# thesis.net
KiCad netlist of a schematic drawn in Altium Designer
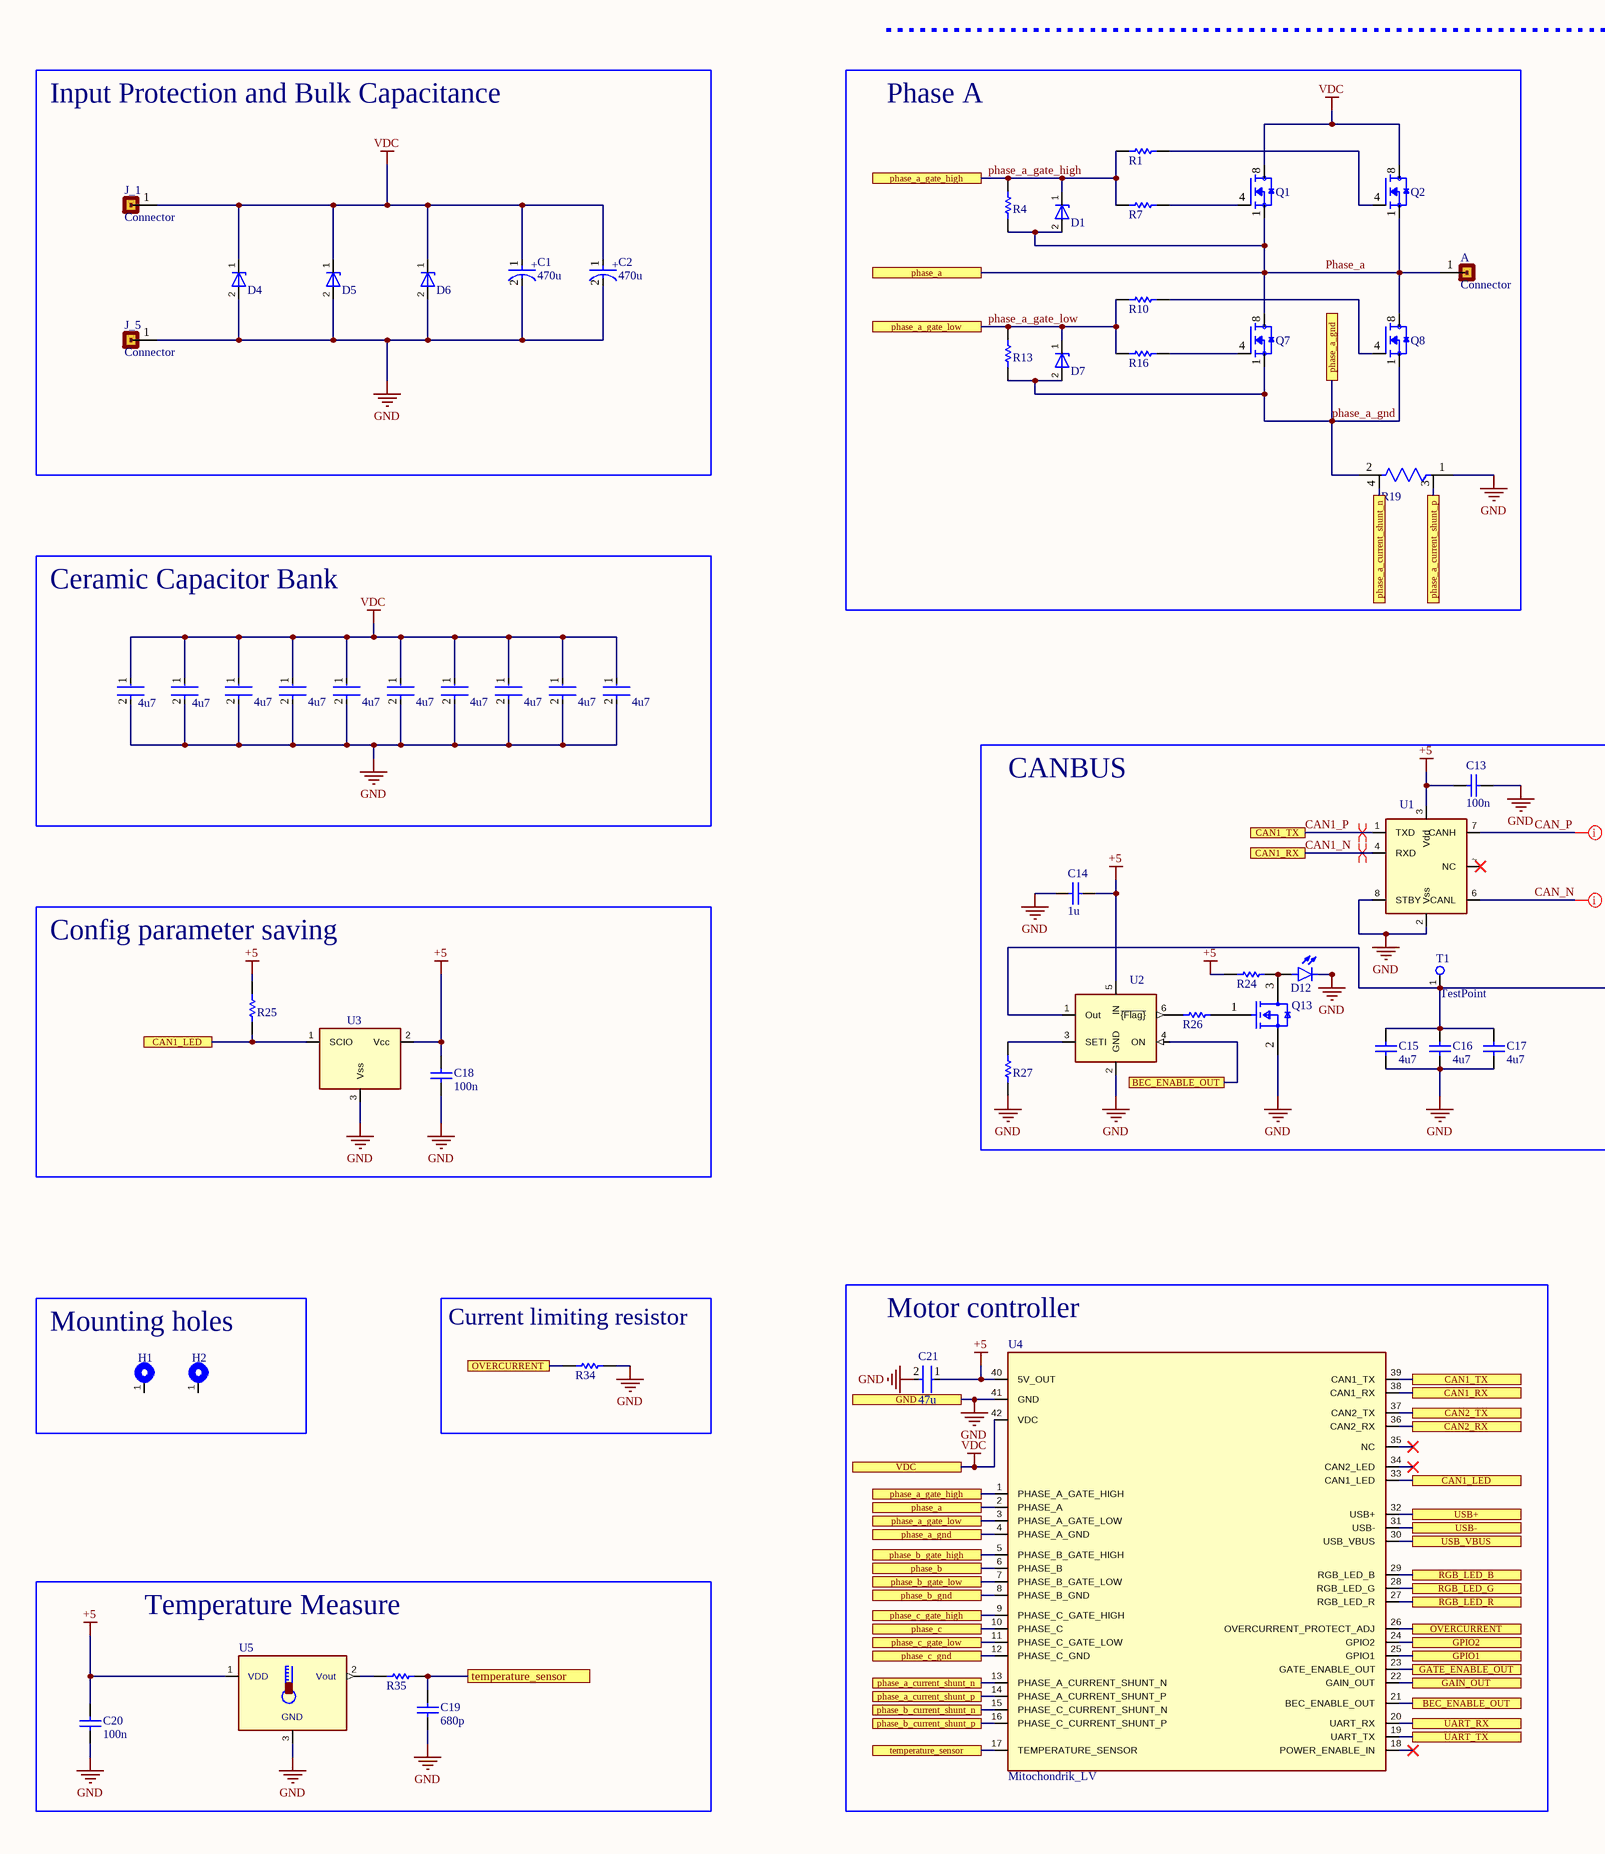
[diagram p0: thesis.SchDoc, left]
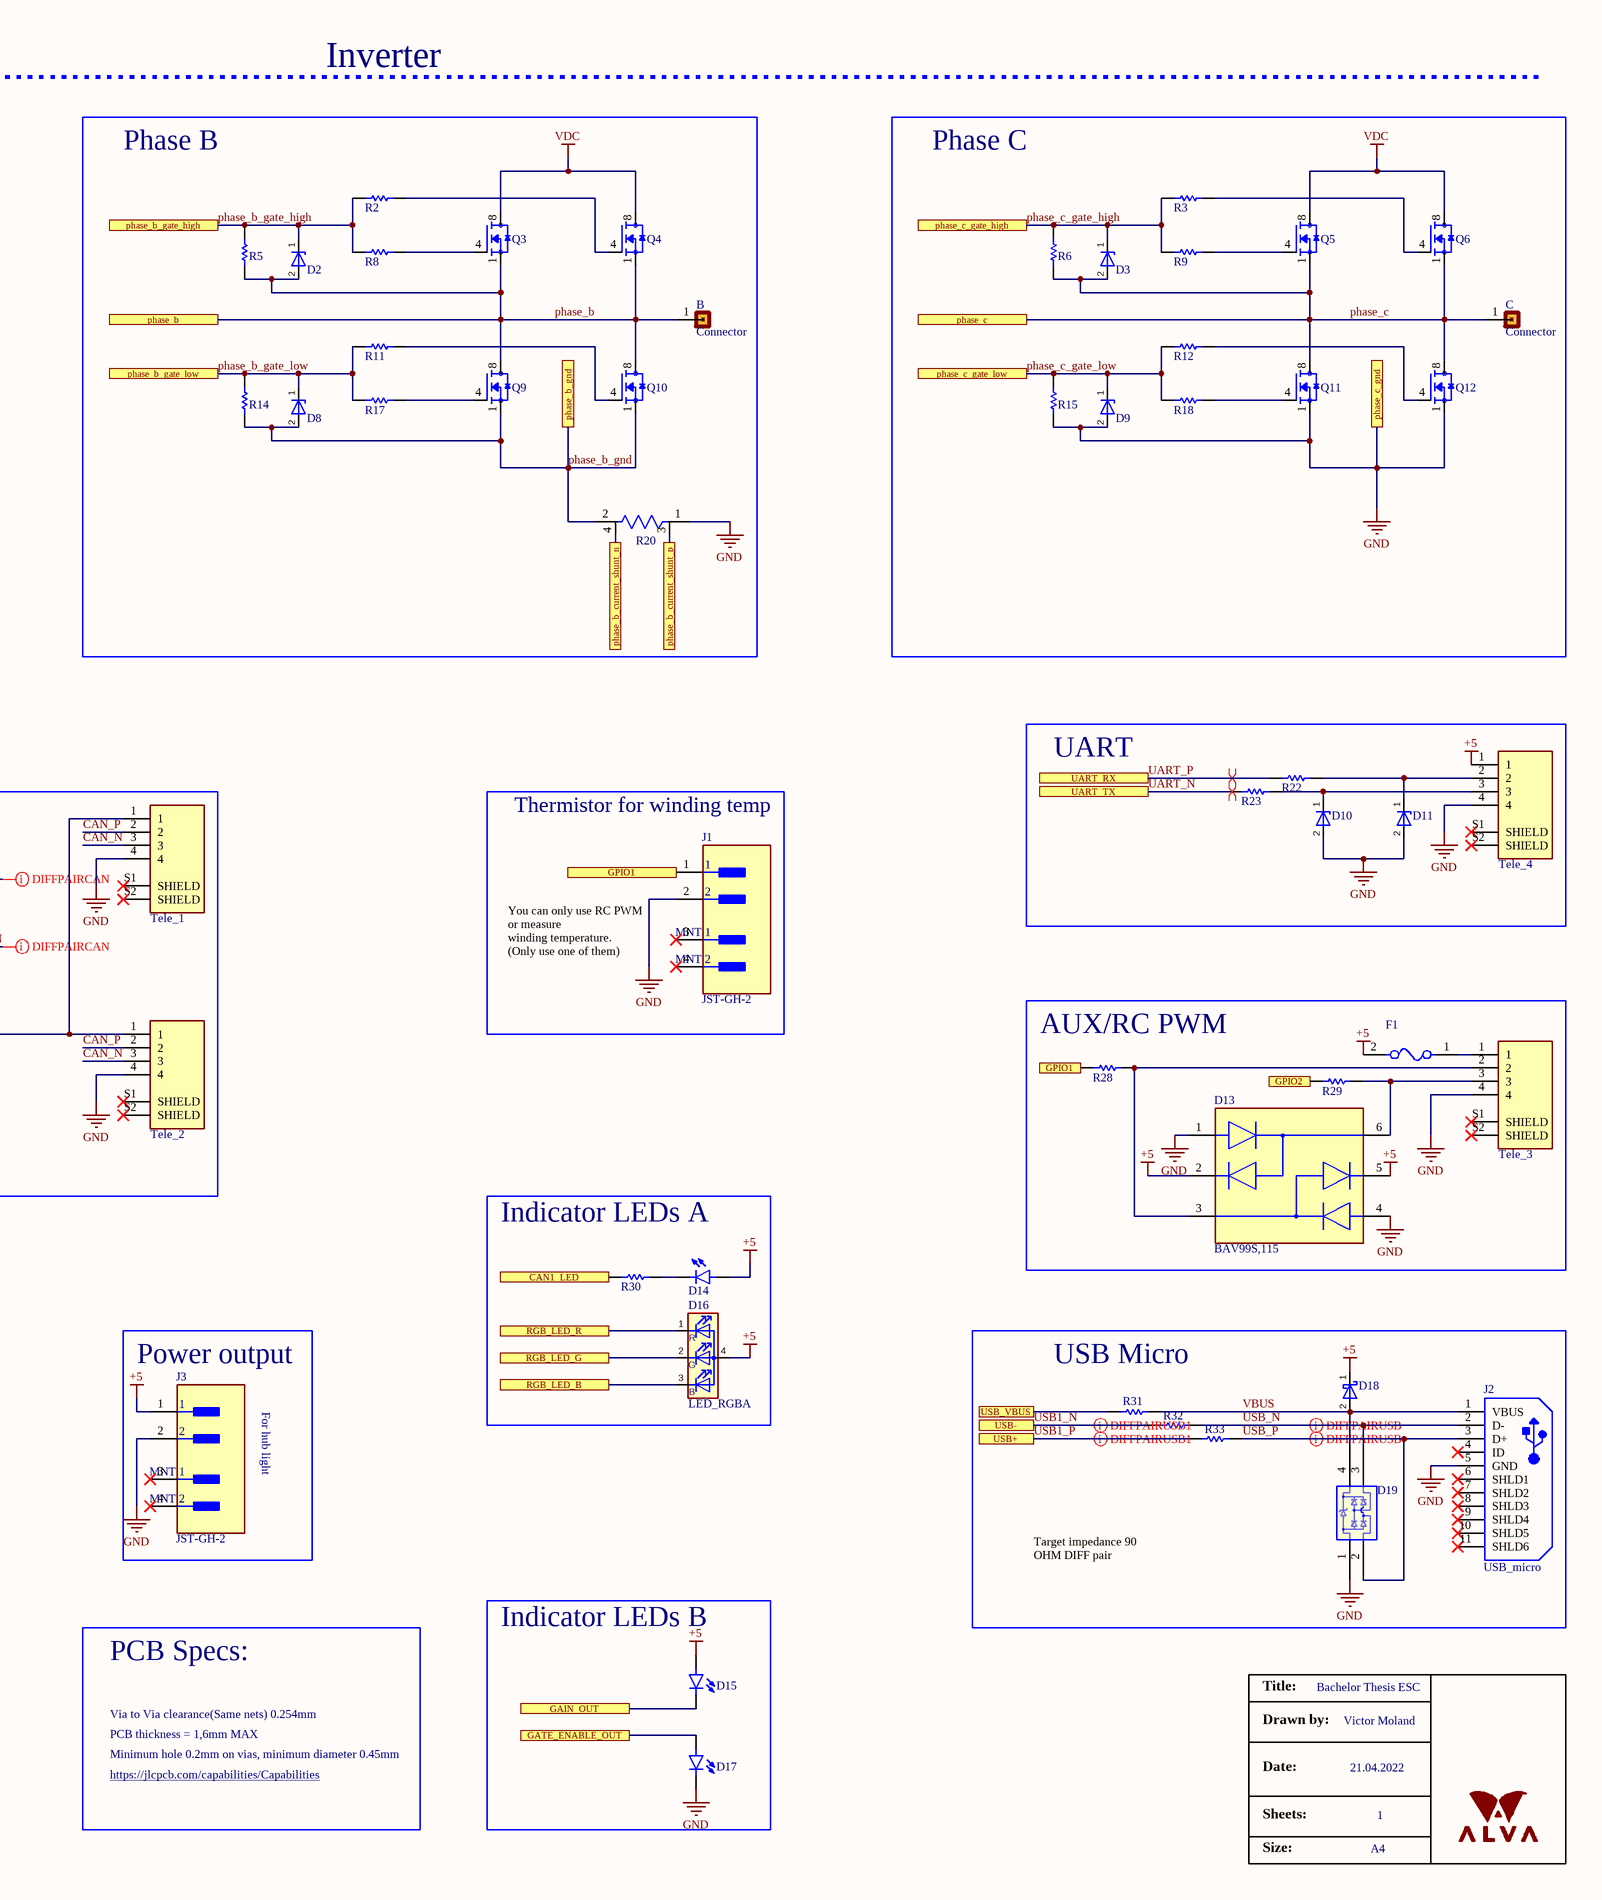
[diagram p1: thesis.SchDoc, right]

(export (version "E")
  (design (tool "Eeschema 10.0.6"))
  (components
    (comp (ref "*") (value "LOGO") (description "ALVA") (libsource (lib "thesis") (part "LOGO")))
    (comp (ref "A")
      (value "Connector")
      (footprint "Conn_01x01")
      (description "Connector 01x01")
      (libsource (lib "") (part "Conn_01x01_1"))
    )
    (comp (ref "B")
      (value "Connector")
      (footprint "Conn_01x01")
      (description "Connector 01x01")
      (libsource (lib "") (part "Conn_01x01_1"))
    )
    (comp (ref "C")
      (value "Connector")
      (footprint "Conn_01x01")
      (description "Connector 01x01")
      (libsource (lib "") (part "Conn_01x01_1"))
    )
    (comp (ref "C1")
      (value "470u")
      (footprint "Cap_radial")
      (fields (field (name "MANUFACTURER") "Panasonic") (field (name "MANUFACTURER PART NUMBER") "ECA1JM471"))
      (libsource (lib "thesis") (part "CAP_Radial"))
    )
    (comp (ref "C2")
      (value "470u")
      (footprint "Cap_radial")
      (fields (field (name "MANUFACTURER") "Panasonic") (field (name "MANUFACTURER PART NUMBER") "ECA1JM471"))
      (libsource (lib "thesis") (part "CAP_Radial"))
    )
    (comp (ref "C3")
      (value "4u7")
      (footprint "Cap_1210")
      (fields
        (field (name "MANUFACTURER") "Murata")
        (field (name "MANUFACTURER PART NUMBER") "GCM32DC72A475KE02L")
      )
      (libsource (lib "thesis") (part "Cap_1210"))
    )
    (comp (ref "C4")
      (value "4u7")
      (footprint "Cap_1210")
      (fields
        (field (name "MANUFACTURER") "Murata")
        (field (name "MANUFACTURER PART NUMBER") "GCM32DC72A475KE02L")
      )
      (libsource (lib "thesis") (part "Cap_1210"))
    )
    (comp (ref "C5")
      (value "4u7")
      (footprint "Cap_1210")
      (fields
        (field (name "MANUFACTURER") "Murata")
        (field (name "MANUFACTURER PART NUMBER") "GCM32DC72A475KE02L")
      )
      (libsource (lib "thesis") (part "Cap_1210"))
    )
    (comp (ref "C6")
      (value "4u7")
      (footprint "Cap_1210")
      (fields
        (field (name "MANUFACTURER") "Murata")
        (field (name "MANUFACTURER PART NUMBER") "GCM32DC72A475KE02L")
      )
      (libsource (lib "thesis") (part "Cap_1210"))
    )
    (comp (ref "C7")
      (value "4u7")
      (footprint "Cap_1210")
      (fields
        (field (name "MANUFACTURER") "Murata")
        (field (name "MANUFACTURER PART NUMBER") "GCM32DC72A475KE02L")
      )
      (libsource (lib "thesis") (part "Cap_1210"))
    )
    (comp (ref "C8")
      (value "4u7")
      (footprint "Cap_1210")
      (fields
        (field (name "MANUFACTURER") "Murata")
        (field (name "MANUFACTURER PART NUMBER") "GCM32DC72A475KE02L")
      )
      (libsource (lib "thesis") (part "Cap_1210"))
    )
    (comp (ref "C9")
      (value "4u7")
      (footprint "Cap_1210")
      (fields
        (field (name "MANUFACTURER") "Murata")
        (field (name "MANUFACTURER PART NUMBER") "GCM32DC72A475KE02L")
      )
      (libsource (lib "thesis") (part "Cap_1210"))
    )
    (comp (ref "C10")
      (value "4u7")
      (footprint "Cap_1210")
      (fields
        (field (name "MANUFACTURER") "Murata")
        (field (name "MANUFACTURER PART NUMBER") "GCM32DC72A475KE02L")
      )
      (libsource (lib "thesis") (part "Cap_1210"))
    )
    (comp (ref "C11")
      (value "4u7")
      (footprint "Cap_1210")
      (fields
        (field (name "MANUFACTURER") "Murata")
        (field (name "MANUFACTURER PART NUMBER") "GCM32DC72A475KE02L")
      )
      (libsource (lib "thesis") (part "Cap_1210"))
    )
    (comp (ref "C12")
      (value "4u7")
      (footprint "Cap_1210")
      (fields
        (field (name "MANUFACTURER") "Murata")
        (field (name "MANUFACTURER PART NUMBER") "GCM32DC72A475KE02L")
      )
      (libsource (lib "thesis") (part "Cap_1210"))
    )
    (comp (ref "C13")
      (value "100n")
      (footprint "CAP_0603")
      (fields
        (field (name "MANUFACTURER") "Kyocera AVX")
        (field (name "MANUFACTURER PART NUMBER") "06033D104KAT2A")
      )
      (libsource (lib "thesis") (part "Cap_0603"))
    )
    (comp (ref "C14")
      (value "1u")
      (footprint "CAP_0603")
      (fields
        (field (name "MANUFACTURER") "Kyocera AVX")
        (field (name "MANUFACTURER PART NUMBER") "0603YD105KAT2A")
      )
      (libsource (lib "thesis") (part "Cap_0603"))
    )
    (comp (ref "C15")
      (value "4u7")
      (footprint "CAP_0603")
      (fields
        (field (name "MANUFACTURER") "Murata")
        (field (name "MANUFACTURER PART NUMBER") "GRT188C81C475KE13D")
      )
      (libsource (lib "thesis") (part "Cap_0603"))
    )
    (comp (ref "C16")
      (value "4u7")
      (footprint "CAP_0603")
      (fields
        (field (name "MANUFACTURER") "Murata")
        (field (name "MANUFACTURER PART NUMBER") "GRT188C81C475KE13D")
      )
      (libsource (lib "thesis") (part "Cap_0603"))
    )
    (comp (ref "C17")
      (value "4u7")
      (footprint "CAP_0603")
      (fields
        (field (name "MANUFACTURER") "Murata")
        (field (name "MANUFACTURER PART NUMBER") "GRT188C81C475KE13D")
      )
      (libsource (lib "thesis") (part "Cap_0603"))
    )
    (comp (ref "C18")
      (value "100n")
      (footprint "CAP_0603")
      (fields
        (field (name "MANUFACTURER") "Kyocera AVX")
        (field (name "MANUFACTURER PART NUMBER") "06033D104KAT2A")
      )
      (libsource (lib "thesis") (part "Cap_0603"))
    )
    (comp (ref "C19")
      (value "680p")
      (footprint "CAP_0603")
      (fields
        (field (name "MANUFACTURER") "Kyocera AVX")
        (field (name "MANUFACTURER PART NUMBER") "06035C681KAT2A")
      )
      (libsource (lib "thesis") (part "Cap_0603"))
    )
    (comp (ref "C20")
      (value "100n")
      (footprint "CAP_0603")
      (fields
        (field (name "MANUFACTURER") "Kyocera AVX")
        (field (name "MANUFACTURER PART NUMBER") "06033D104KAT2A")
      )
      (libsource (lib "thesis") (part "Cap_0603"))
    )
    (comp (ref "C21")
      (value "47u")
      (footprint "Cap_1210")
      (fields
        (field (name "MANUFACTURER") "Murata")
        (field (name "MANUFACTURER PART NUMBER") "GRM32ER71A476ME15L")
      )
      (libsource (lib "thesis") (part "Cap_1210"))
    )
    (comp (ref "D1")
      (value "BZD27C16PWHCT-ND")
      (footprint "Zener_16V")
      (fields
        (field (name "MANUFACTURER") "Taiwan Semiconductor")
        (field (name "MANUFACTURER PART NUMBER") "BZD27C16PWH")
      )
      (libsource (lib "thesis") (part "Zener_16V"))
    )
    (comp (ref "D2")
      (value "BZD27C16PWHCT-ND")
      (footprint "Zener_16V")
      (fields
        (field (name "MANUFACTURER") "Taiwan Semiconductor")
        (field (name "MANUFACTURER PART NUMBER") "BZD27C16PWH")
      )
      (libsource (lib "thesis") (part "Zener_16V"))
    )
    (comp (ref "D3")
      (value "BZD27C16PWHCT-ND")
      (footprint "Zener_16V")
      (fields
        (field (name "MANUFACTURER") "Taiwan Semiconductor")
        (field (name "MANUFACTURER PART NUMBER") "BZD27C16PWH")
      )
      (libsource (lib "thesis") (part "Zener_16V"))
    )
    (comp (ref "D4")
      (value "SMC5K51A-M3/IGICT-ND")
      (footprint "Zener_51V")
      (description "Trans Voltage Suppressor Diode, 5000W, 51V V(RWM), Unidirectional, 1 Element, Silicon, DO-214AB")
      (fields
        (field (name "MANUFACTURER") "Vishay")
        (field (name "MANUFACTURER PART NUMBER") "SMC5K51A-M3/I")
      )
      (libsource (lib "thesis") (part "Zener_51V"))
    )
    (comp (ref "D5")
      (value "SMC5K51A-M3/IGICT-ND")
      (footprint "Zener_51V")
      (description "Trans Voltage Suppressor Diode, 5000W, 51V V(RWM), Unidirectional, 1 Element, Silicon, DO-214AB")
      (fields
        (field (name "MANUFACTURER") "Vishay")
        (field (name "MANUFACTURER PART NUMBER") "SMC5K51A-M3/I")
      )
      (libsource (lib "thesis") (part "Zener_51V"))
    )
    (comp (ref "D6")
      (value "SMC5K51A-M3/IGICT-ND")
      (footprint "Zener_51V")
      (description "Trans Voltage Suppressor Diode, 5000W, 51V V(RWM), Unidirectional, 1 Element, Silicon, DO-214AB")
      (fields
        (field (name "MANUFACTURER") "Vishay")
        (field (name "MANUFACTURER PART NUMBER") "SMC5K51A-M3/I")
      )
      (libsource (lib "thesis") (part "Zener_51V"))
    )
    (comp (ref "D7")
      (value "BZD27C16PWHCT-ND")
      (footprint "Zener_16V")
      (fields
        (field (name "MANUFACTURER") "Taiwan Semiconductor")
        (field (name "MANUFACTURER PART NUMBER") "BZD27C16PWH")
      )
      (libsource (lib "thesis") (part "Zener_16V"))
    )
    (comp (ref "D8")
      (value "BZD27C16PWHCT-ND")
      (footprint "Zener_16V")
      (fields
        (field (name "MANUFACTURER") "Taiwan Semiconductor")
        (field (name "MANUFACTURER PART NUMBER") "BZD27C16PWH")
      )
      (libsource (lib "thesis") (part "Zener_16V"))
    )
    (comp (ref "D9")
      (value "BZD27C16PWHCT-ND")
      (footprint "Zener_16V")
      (fields
        (field (name "MANUFACTURER") "Taiwan Semiconductor")
        (field (name "MANUFACTURER PART NUMBER") "BZD27C16PWH")
      )
      (libsource (lib "thesis") (part "Zener_16V"))
    )
    (comp (ref "D10")
      (value "SMF5.0A-TPMSCT-ND")
      (footprint "Zener_5V")
      (description "Trans Voltage Suppressor Diode, 200W, 5V V(RWM), Unidirectional, 1 Element, Silicon")
      (fields (field (name "MANUFACTURER") "MCC") (field (name "MANUFACTURER PART NUMBER") "SMF5.0A-TP"))
      (libsource (lib "thesis") (part "Zener_5V"))
    )
    (comp (ref "D11")
      (value "SMF5.0A-TPMSCT-ND")
      (footprint "Zener_5V")
      (description "Trans Voltage Suppressor Diode, 200W, 5V V(RWM), Unidirectional, 1 Element, Silicon")
      (fields (field (name "MANUFACTURER") "MCC") (field (name "MANUFACTURER PART NUMBER") "SMF5.0A-TP"))
      (libsource (lib "thesis") (part "Zener_5V"))
    )
    (comp (ref "D12")
      (value "LED0603(LTW-C193TS5)")
      (footprint "LED0603")
      (description "Top View / 0402 / 1.0X0.5X0.4")
      (fields (field (name "MANUFACTURER") "Inolux") (field (name "MANUFACTURER PART NUMBER") "IN-S42BTR"))
      (libsource (lib "thesis") (part "LED0603(LTW-C193TS5)"))
    )
    (comp (ref "D13")
      (value "BAV99S,115")
      (footprint "BAV99S")
      (description "Rectifier Diode, 4 Element, 0.2A, 85V V(RRM), Silicon")
      (fields (field (name "MANUFACTURER") "Infineon") (field (name "MANUFACTURER PART NUMBER") "BAV99S"))
      (libsource (lib "thesis") (part "BAV99S"))
    )
    (comp (ref "D14")
      (value "LED0603(LTW-C193TS5)")
      (footprint "LED0603")
      (description "White LED Indication - Discrete 2.93V 0603 (1608 Metric)")
      (fields (field (name "MANUFACTURER") "Inolux") (field (name "MANUFACTURER PART NUMBER") "IN-S42BT5G"))
      (libsource (lib "thesis") (part "LED0603(LTW-C193TS5)"))
    )
    (comp (ref "D15")
      (value "LED0603(LTW-C193TS5)")
      (footprint "LED0603")
      (description "Top View / 0402 / 1.0X0.5X0.4")
      (fields (field (name "MANUFACTURER") "Inolux") (field (name "MANUFACTURER PART NUMBER") "IN-S42BTR"))
      (libsource (lib "thesis") (part "LED0603(LTW-C193TS5)"))
    )
    (comp (ref "D16")
      (value "LED_RGBA")
      (footprint "LED_0606")
      (description "LED RGB 0606 SMD")
      (fields
        (field (name "MANUFACTURER") "Dialight")
        (field (name "MANUFACTURER PART NUMBER") "5977715607F")
      )
      (libsource (lib "thesis") (part "LED_RGBA"))
    )
    (comp (ref "D17")
      (value "LED0603(LTW-C193TS5)")
      (footprint "LED0603")
      (description "White LED Indication - Discrete 2.93V 0603 (1608 Metric)")
      (fields (field (name "MANUFACTURER") "Inolux") (field (name "MANUFACTURER PART NUMBER") "IN-S42BT5G"))
      (libsource (lib "thesis") (part "LED0603(LTW-C193TS5)"))
    )
    (comp (ref "D18")
      (value "PMEG2010AEH")
      (footprint "PMEG2010AEH")
      (description "Rectifier Diode, Schottky, 1 Phase, 1 Element, 1A, Silicon")
      (fields
        (field (name "MANUFACTURER") "Nexperia")
        (field (name "MANUFACTURER PART NUMBER") "PMEG2010AEH,115")
      )
      (libsource (lib "thesis") (part "PMEG2010AEH"))
    )
    (comp (ref "D19")
      (value "DRTR5V0U2SR-7")
      (footprint "DRTR5V0OU2SR-7")
      (description "Trans Voltage Suppressor Diode, 5.5V V(RWM), Unidirectional, 1 Element, Silicon")
      (fields (field (name "MANUFACTURER") "Diodes"))
      (libsource (lib "thesis") (part "DRTR5V0U2SR-7"))
    )
    (comp (ref "F1")
      (value "Polyfuse")
      (footprint "Polyfuse")
      (description "PTC Resettable Fuse, 60V, Surface Mount")
      (fields (field (name "MANUFACTURER") "Bourns") (field (name "MANUFACTURER PART NUMBER") "MF-MSMF014-2"))
      (libsource (lib "thesis") (part "Polyfuse"))
    )
    (comp (ref "H1")
      (value "MountingHole_Pad")
      (footprint "Mounting_holes")
      (description "Mounting hole")
      (libsource (lib "thesis") (part "MountingHole_Pad"))
    )
    (comp (ref "H2")
      (value "MountingHole_Pad")
      (footprint "Mounting_holes")
      (description "Mounting hole")
      (libsource (lib "thesis") (part "MountingHole_Pad"))
    )
    (comp (ref "J1")
      (value "JST-GH-2")
      (footprint "JST-GH-2")
      (description "Connector Header, GH Series, 2 Position, 1.25mm, 50V, Surface Mount, Locking Ramp, Natural")
      (fields
        (field (name "MANUFACTURER") "JST")
        (field (name "MANUFACTURER PART NUMBER") "BM02B-GHS-TBT(LF)(SN)(N)")
      )
      (libsource (lib "thesis") (part "JST-GH-2"))
    )
    (comp (ref "J2")
      (value "USB_micro")
      (footprint "USB_micro")
      (description "USB Connector, 5 Contact(s), Female, Right Angle, Surface Mount Terminal, Locking, Receptacle")
      (fields (field (name "MANUFACTURER") "Molex") (field (name "MANUFACTURER PART NUMBER") "47589-0001"))
      (libsource (lib "thesis") (part "USB_micro"))
    )
    (comp (ref "J3")
      (value "JST-GH-2")
      (footprint "JST-GH-2")
      (description "Connector Header, GH Series, 2 Position, 1.25mm, 50V, Surface Mount, Locking Ramp, Natural")
      (fields
        (field (name "MANUFACTURER") "JST")
        (field (name "MANUFACTURER PART NUMBER") "BM02B-GHS-TBT(LF)(SN)(N)")
      )
      (libsource (lib "thesis") (part "JST-GH-2"))
    )
    (comp (ref "J_1")
      (value "Connector")
      (footprint "Conn_01x01")
      (description "Connector 01x01")
      (libsource (lib "thesis") (part "Conn_01x01"))
    )
    (comp (ref "J_5")
      (value "Connector")
      (footprint "Conn_01x01")
      (description "Connector 01x01")
      (libsource (lib "thesis") (part "Conn_01x01"))
    )
    (comp (ref "Q1")
      (value "BSC021N08NS5ATMA1")
      (footprint "BSC021N08NS5ATMA1")
      (description "N-Channel 80V 100A (Tc) 214W (Tc) Surface Mount PG-TSON-8-3")
      (fields (field (name "MANUFACTURER") "Infineon"))
      (libsource (lib "thesis") (part "BSC021N08NS5ATMA1"))
    )
    (comp (ref "Q2")
      (value "BSC021N08NS5ATMA1")
      (footprint "BSC021N08NS5ATMA1")
      (description "N-Channel 80V 100A (Tc) 214W (Tc) Surface Mount PG-TSON-8-3")
      (fields (field (name "MANUFACTURER") "Infineon"))
      (libsource (lib "thesis") (part "BSC021N08NS5ATMA1"))
    )
    (comp (ref "Q3")
      (value "BSC021N08NS5ATMA1")
      (footprint "BSC021N08NS5ATMA1")
      (description "N-Channel 80V 100A (Tc) 214W (Tc) Surface Mount PG-TSON-8-3")
      (fields (field (name "MANUFACTURER") "Infineon"))
      (libsource (lib "thesis") (part "BSC021N08NS5ATMA1"))
    )
    (comp (ref "Q4")
      (value "BSC021N08NS5ATMA1")
      (footprint "BSC021N08NS5ATMA1")
      (description "N-Channel 80V 100A (Tc) 214W (Tc) Surface Mount PG-TSON-8-3")
      (fields (field (name "MANUFACTURER") "Infineon"))
      (libsource (lib "thesis") (part "BSC021N08NS5ATMA1"))
    )
    (comp (ref "Q5")
      (value "BSC021N08NS5ATMA1")
      (footprint "BSC021N08NS5ATMA1")
      (description "N-Channel 80V 100A (Tc) 214W (Tc) Surface Mount PG-TSON-8-3")
      (fields (field (name "MANUFACTURER") "Infineon"))
      (libsource (lib "thesis") (part "BSC021N08NS5ATMA1"))
    )
    (comp (ref "Q6")
      (value "BSC021N08NS5ATMA1")
      (footprint "BSC021N08NS5ATMA1")
      (description "N-Channel 80V 100A (Tc) 214W (Tc) Surface Mount PG-TSON-8-3")
      (fields (field (name "MANUFACTURER") "Infineon"))
      (libsource (lib "thesis") (part "BSC021N08NS5ATMA1"))
    )
    (comp (ref "Q7")
      (value "BSC021N08NS5ATMA1")
      (footprint "BSC021N08NS5ATMA1")
      (description "N-Channel 80V 100A (Tc) 214W (Tc) Surface Mount PG-TSON-8-3")
      (fields (field (name "MANUFACTURER") "Infineon"))
      (libsource (lib "thesis") (part "BSC021N08NS5ATMA1"))
    )
    (comp (ref "Q8")
      (value "BSC021N08NS5ATMA1")
      (footprint "BSC021N08NS5ATMA1")
      (description "N-Channel 80V 100A (Tc) 214W (Tc) Surface Mount PG-TSON-8-3")
      (fields (field (name "MANUFACTURER") "Infineon"))
      (libsource (lib "thesis") (part "BSC021N08NS5ATMA1"))
    )
    (comp (ref "Q9")
      (value "BSC021N08NS5ATMA1")
      (footprint "BSC021N08NS5ATMA1")
      (description "N-Channel 80V 100A (Tc) 214W (Tc) Surface Mount PG-TSON-8-3")
      (fields (field (name "MANUFACTURER") "Infineon"))
      (libsource (lib "thesis") (part "BSC021N08NS5ATMA1"))
    )
    (comp (ref "Q10")
      (value "BSC021N08NS5ATMA1")
      (footprint "BSC021N08NS5ATMA1")
      (description "N-Channel 80V 100A (Tc) 214W (Tc) Surface Mount PG-TSON-8-3")
      (fields (field (name "MANUFACTURER") "Infineon"))
      (libsource (lib "thesis") (part "BSC021N08NS5ATMA1"))
    )
    (comp (ref "Q11")
      (value "BSC021N08NS5ATMA1")
      (footprint "BSC021N08NS5ATMA1")
      (description "N-Channel 80V 100A (Tc) 214W (Tc) Surface Mount PG-TSON-8-3")
      (fields (field (name "MANUFACTURER") "Infineon"))
      (libsource (lib "thesis") (part "BSC021N08NS5ATMA1"))
    )
    (comp (ref "Q12")
      (value "BSC021N08NS5ATMA1")
      (footprint "BSC021N08NS5ATMA1")
      (description "N-Channel 80V 100A (Tc) 214W (Tc) Surface Mount PG-TSON-8-3")
      (fields (field (name "MANUFACTURER") "Infineon"))
      (libsource (lib "thesis") (part "BSC021N08NS5ATMA1"))
    )
    (comp (ref "Q13")
      (value "BSS138")
      (footprint "BSS138")
      (fields
        (field (name "MANUFACTURER") "Infineon")
        (field (name "MANUFACTURER PART NUMBER") "BSS138WH6433XTMA1")
      )
      (libsource (lib "thesis") (part "BSS138"))
    )
    (comp (ref "R1")
      (value "4R3")
      (footprint "Res_0603")
      (description "Res SMD 4.3 Ohm 5% 1/4W 0603")
      (fields
        (field (name "MANUFACTURER") "Panasonic")
        (field (name "MANUFACTURER PART NUMBER") "ERJ-PA3J4R3V")
      )
      (libsource (lib "thesis") (part "RES_0603"))
    )
    (comp (ref "R2")
      (value "4R3")
      (footprint "Res_0603")
      (description "Res SMD 4.3 Ohm 5% 1/4W 0603")
      (fields
        (field (name "MANUFACTURER") "Panasonic")
        (field (name "MANUFACTURER PART NUMBER") "ERJ-PA3J4R3V")
      )
      (libsource (lib "thesis") (part "RES_0603"))
    )
    (comp (ref "R3")
      (value "4R3")
      (footprint "Res_0603")
      (description "Res SMD 4.3 Ohm 5% 1/4W 0603")
      (fields
        (field (name "MANUFACTURER") "Panasonic")
        (field (name "MANUFACTURER PART NUMBER") "ERJ-PA3J4R3V")
      )
      (libsource (lib "thesis") (part "RES_0603"))
    )
    (comp (ref "R4")
      (value "100k")
      (footprint "Res_0603")
      (description "Chip Resistor")
      (fields
        (field (name "MANUFACTURER") "Panasonic")
        (field (name "MANUFACTURER PART NUMBER") "ERJ-UP3J104V")
      )
      (libsource (lib "thesis") (part "RES_0603"))
    )
    (comp (ref "R5")
      (value "100k")
      (footprint "Res_0603")
      (description "Chip Resistor")
      (fields
        (field (name "MANUFACTURER") "Panasonic")
        (field (name "MANUFACTURER PART NUMBER") "ERJ-UP3J104V")
      )
      (libsource (lib "thesis") (part "RES_0603"))
    )
    (comp (ref "R6")
      (value "100k")
      (footprint "Res_0603")
      (description "Chip Resistor")
      (fields
        (field (name "MANUFACTURER") "Panasonic")
        (field (name "MANUFACTURER PART NUMBER") "ERJ-UP3J104V")
      )
      (libsource (lib "thesis") (part "RES_0603"))
    )
    (comp (ref "R7")
      (value "4R3")
      (footprint "Res_0603")
      (description "Res SMD 4.3 Ohm 5% 1/4W 0603")
      (fields
        (field (name "MANUFACTURER") "Panasonic")
        (field (name "MANUFACTURER PART NUMBER") "ERJ-PA3J4R3V")
      )
      (libsource (lib "thesis") (part "RES_0603"))
    )
    (comp (ref "R8")
      (value "4R3")
      (footprint "Res_0603")
      (description "Res SMD 4.3 Ohm 5% 1/4W 0603")
      (fields
        (field (name "MANUFACTURER") "Panasonic")
        (field (name "MANUFACTURER PART NUMBER") "ERJ-PA3J4R3V")
      )
      (libsource (lib "thesis") (part "RES_0603"))
    )
    (comp (ref "R9")
      (value "4R3")
      (footprint "Res_0603")
      (description "Res SMD 4.3 Ohm 5% 1/4W 0603")
      (fields
        (field (name "MANUFACTURER") "Panasonic")
        (field (name "MANUFACTURER PART NUMBER") "ERJ-PA3J4R3V")
      )
      (libsource (lib "thesis") (part "RES_0603"))
    )
    (comp (ref "R10")
      (value "4R3")
      (footprint "Res_0603")
      (description "Res SMD 4.3 Ohm 5% 1/4W 0603")
      (fields
        (field (name "MANUFACTURER") "Panasonic")
        (field (name "MANUFACTURER PART NUMBER") "ERJ-PA3J4R3V")
      )
      (libsource (lib "thesis") (part "RES_0603"))
    )
    (comp (ref "R11")
      (value "4R3")
      (footprint "Res_0603")
      (description "Res SMD 4.3 Ohm 5% 1/4W 0603")
      (fields
        (field (name "MANUFACTURER") "Panasonic")
        (field (name "MANUFACTURER PART NUMBER") "ERJ-PA3J4R3V")
      )
      (libsource (lib "thesis") (part "RES_0603"))
    )
    (comp (ref "R12")
      (value "4R3")
      (footprint "Res_0603")
      (description "Res SMD 4.3 Ohm 5% 1/4W 0603")
      (fields
        (field (name "MANUFACTURER") "Panasonic")
        (field (name "MANUFACTURER PART NUMBER") "ERJ-PA3J4R3V")
      )
      (libsource (lib "thesis") (part "RES_0603"))
    )
    (comp (ref "R13")
      (value "100k")
      (footprint "Res_0603")
      (description "Chip Resistor")
      (fields
        (field (name "MANUFACTURER") "Panasonic")
        (field (name "MANUFACTURER PART NUMBER") "ERJ-UP3J104V")
      )
      (libsource (lib "thesis") (part "RES_0603"))
    )
    (comp (ref "R14")
      (value "100k")
      (footprint "Res_0603")
      (description "Chip Resistor")
      (fields
        (field (name "MANUFACTURER") "Panasonic")
        (field (name "MANUFACTURER PART NUMBER") "ERJ-UP3J104V")
      )
      (libsource (lib "thesis") (part "RES_0603"))
    )
    (comp (ref "R15")
      (value "100k")
      (footprint "Res_0603")
      (description "Chip Resistor")
      (fields
        (field (name "MANUFACTURER") "Panasonic")
        (field (name "MANUFACTURER PART NUMBER") "ERJ-UP3J104V")
      )
      (libsource (lib "thesis") (part "RES_0603"))
    )
    (comp (ref "R16")
      (value "4R3")
      (footprint "Res_0603")
      (description "Res SMD 4.3 Ohm 5% 1/4W 0603")
      (fields
        (field (name "MANUFACTURER") "Panasonic")
        (field (name "MANUFACTURER PART NUMBER") "ERJ-PA3J4R3V")
      )
      (libsource (lib "thesis") (part "RES_0603"))
    )
    (comp (ref "R17")
      (value "4R3")
      (footprint "Res_0603")
      (description "Res SMD 4.3 Ohm 5% 1/4W 0603")
      (fields
        (field (name "MANUFACTURER") "Panasonic")
        (field (name "MANUFACTURER PART NUMBER") "ERJ-PA3J4R3V")
      )
      (libsource (lib "thesis") (part "RES_0603"))
    )
    (comp (ref "R18")
      (value "4R3")
      (footprint "Res_0603")
      (description "Res SMD 4.3 Ohm 5% 1/4W 0603")
      (fields
        (field (name "MANUFACTURER") "Panasonic")
        (field (name "MANUFACTURER PART NUMBER") "ERJ-PA3J4R3V")
      )
      (libsource (lib "thesis") (part "RES_0603"))
    )
    (comp (ref "R19")
      (value "2mOhm")
      (footprint "Shunt_res")
      (description "Fixed Resistor, Metal Strip, 3W, 0.002ohm, 0.077V, 1% +/-Tol, 275ppm/Cel, Surface Mount, 2512")
      (fields
        (field (name "MANUFACTURER") "Vishay Dale")
        (field (name "MANUFACTURER PART NUMBER") "WSLP25122L000FEA")
      )
      (libsource (lib "thesis") (part "Shunt_res"))
    )
    (comp (ref "R20")
      (value "2mOhm")
      (footprint "Shunt_res")
      (description "Fixed Resistor, Metal Strip, 3W, 0.002ohm, 0.077V, 1% +/-Tol, 275ppm/Cel, Surface Mount, 2512")
      (fields
        (field (name "MANUFACTURER") "Vishay Dale")
        (field (name "MANUFACTURER PART NUMBER") "WSLP25122L000FEA")
      )
      (libsource (lib "thesis") (part "Shunt_res"))
    )
    (comp (ref "R22")
      (value "4R3")
      (footprint "Res_0603")
      (fields
        (field (name "MANUFACTURER") "Panasonic")
        (field (name "MANUFACTURER PART NUMBER") "ERJ-U03F4R30V")
      )
      (libsource (lib "thesis") (part "RES_0603"))
    )
    (comp (ref "R23")
      (value "4R3")
      (footprint "Res_0603")
      (fields
        (field (name "MANUFACTURER") "Panasonic")
        (field (name "MANUFACTURER PART NUMBER") "ERJ-U03F4R30V")
      )
      (libsource (lib "thesis") (part "RES_0603"))
    )
    (comp (ref "R24")
      (value "1k")
      (footprint "Res_0603")
      (fields
        (field (name "MANUFACTURER") "Panasonic")
        (field (name "MANUFACTURER PART NUMBER") "ERJ3EKF1001V")
        (field (name "TOLERANCE") "1%")
      )
      (libsource (lib "thesis") (part "RES_0603"))
    )
    (comp (ref "R25")
      (value "1k")
      (footprint "Res_0603")
      (fields
        (field (name "MANUFACTURER") "Panasonic")
        (field (name "MANUFACTURER PART NUMBER") "ERJ3EKF1001V")
        (field (name "TOLERANCE") "1%")
      )
      (libsource (lib "thesis") (part "RES_0603"))
    )
    (comp (ref "R26")
      (value "200Ohm")
      (footprint "Res_0603")
      (fields
        (field (name "MANUFACTURER") "Rohm")
        (field (name "MANUFACTURER PART NUMBER") "ESR03EZPF2000")
        (field (name "TOLERANCE") "1%")
      )
      (libsource (lib "thesis") (part "RES_0603"))
    )
    (comp (ref "R27")
      (value "46k4")
      (footprint "Res_0603")
      (description "Fixed Resistor, Thin Film, 0.1W, 45900ohm, 75V, 1% +/-Tol, 100ppm/Cel, Surface Mount, 0603")
      (fields
        (field (name "MANUFACTURER") "KOA Speer")
        (field (name "MANUFACTURER PART NUMBER") "RN73H1JTTD4592F100")
      )
      (libsource (lib "thesis") (part "RES_0603"))
    )
    (comp (ref "R28")
      (value "100Ohm")
      (footprint "Res_0603")
      (description "Chip Resistor")
      (fields
        (field (name "MANUFACTURER") "Panasonic")
        (field (name "MANUFACTURER PART NUMBER") "ERJ-UP3F1000V")
      )
      (libsource (lib "thesis") (part "RES_0603"))
    )
    (comp (ref "R29")
      (value "100Ohm")
      (footprint "Res_0603")
      (description "Chip Resistor")
      (fields
        (field (name "MANUFACTURER") "Panasonic")
        (field (name "MANUFACTURER PART NUMBER") "ERJ-UP3F1000V")
      )
      (libsource (lib "thesis") (part "RES_0603"))
    )
    (comp (ref "R30")
      (value "1k")
      (footprint "Res_0603")
      (fields
        (field (name "MANUFACTURER") "Panasonic")
        (field (name "MANUFACTURER PART NUMBER") "ERJ3EKF1001V")
        (field (name "TOLERANCE") "1%")
      )
      (libsource (lib "thesis") (part "RES_0603"))
    )
    (comp (ref "R31")
      (value "1k")
      (footprint "Res_0603")
      (fields
        (field (name "MANUFACTURER") "Panasonic")
        (field (name "MANUFACTURER PART NUMBER") "ERJ3EKF1001V")
        (field (name "TOLERANCE") "1%")
      )
      (libsource (lib "thesis") (part "RES_0603"))
    )
    (comp (ref "R32")
      (value "4R3")
      (footprint "Res_0603")
      (fields
        (field (name "MANUFACTURER") "Panasonic")
        (field (name "MANUFACTURER PART NUMBER") "ERJ-U03F4R30V")
      )
      (libsource (lib "thesis") (part "RES_0603"))
    )
    (comp (ref "R33")
      (value "4R3")
      (footprint "Res_0603")
      (fields
        (field (name "MANUFACTURER") "Panasonic")
        (field (name "MANUFACTURER PART NUMBER") "ERJ-U03F4R30V")
      )
      (libsource (lib "thesis") (part "RES_0603"))
    )
    (comp (ref "R34")
      (value "R_curr")
      (footprint "Res_0603")
      (fields
        (field (name "MANUFACTURER") "Panasonic")
        (field (name "MANUFACTURER PART NUMBER") "ERJ-3EKF5100V")
        (field (name "TOLERANCE") "1%")
      )
      (libsource (lib "thesis") (part "RES_0603"))
    )
    (comp (ref "R35")
      (value "R_filter")
      (footprint "Res_0603")
      (fields
        (field (name "MANUFACTURER") "Panasonic")
        (field (name "MANUFACTURER PART NUMBER") "ERJ-3EKF15R0V")
        (field (name "TOLERANCE") "1%")
      )
      (libsource (lib "thesis") (part "RES_0603"))
    )
    (comp (ref "T1")
      (value "TestPoint")
      (footprint "Testpoint")
      (description "Testpoint")
      (libsource (lib "thesis") (part "TestPoint"))
    )
    (comp (ref "Tele_1")
      (value "JST-GH-4")
      (footprint "JST-GH-4")
      (description "Conn Shrouded Header HDR 4 POS 1.25mm Solder ST Top Entry SMD T/R")
      (fields
        (field (name "MANUFACTURER") "JST")
        (field (name "MANUFACTURER PART NUMBER") "BM04B-GHS-TBT(LF)(SN)(N)")
      )
      (libsource (lib "thesis") (part "JST-GH-4"))
    )
    (comp (ref "Tele_2")
      (value "JST-GH-4")
      (footprint "JST-GH-4")
      (description "Conn Shrouded Header HDR 4 POS 1.25mm Solder ST Top Entry SMD T/R")
      (fields
        (field (name "MANUFACTURER") "JST")
        (field (name "MANUFACTURER PART NUMBER") "BM04B-GHS-TBT(LF)(SN)(N)")
      )
      (libsource (lib "thesis") (part "JST-GH-4"))
    )
    (comp (ref "Tele_3")
      (value "JST-GH-4")
      (footprint "JST-GH-4")
      (description "Conn Shrouded Header HDR 4 POS 1.25mm Solder ST Top Entry SMD T/R")
      (fields
        (field (name "MANUFACTURER") "JST")
        (field (name "MANUFACTURER PART NUMBER") "BM04B-GHS-TBT(LF)(SN)(N)")
      )
      (libsource (lib "thesis") (part "JST-GH-4"))
    )
    (comp (ref "Tele_4")
      (value "JST-GH-4")
      (footprint "JST-GH-4")
      (description "Conn Shrouded Header HDR 4 POS 1.25mm Solder ST Top Entry SMD T/R")
      (fields
        (field (name "MANUFACTURER") "JST")
        (field (name "MANUFACTURER PART NUMBER") "BM04B-GHS-TBT(LF)(SN)(N)")
      )
      (libsource (lib "thesis") (part "JST-GH-4"))
    )
    (comp (ref "U1")
      (value "MCP2544FDT-E_MNY")
      (footprint "MCP2544FDT-E_MNY")
      (description "Interface Circuit, PDSO8")
      (fields
        (field (name "MANUFACTURER") "Microchip")
        (field (name "MANUFACTURER PART NUMBER") "MCP2544FDT-E/MNY")
      )
      (libsource (lib "thesis") (part "MCP2544FDT-E_MNY"))
    )
    (comp (ref "U2")
      (value "MAX4995A")
      (footprint "MAX4995AAUT+T")
      (description "Analog Circuit, 1 Func, BICMOS, PDSO6")
      (fields (field (name "MANUFACTURER") "Maxim") (field (name "MANUFACTURER PART NUMBER") "MAX4995AAUT+T"))
      (libsource (lib "thesis") (part "MAX4995A"))
    )
    (comp (ref "U3")
      (value "11LC040T-E/TTTR-ND")
      (footprint "11LC040T-E/TTTR-ND")
      (description "EEPROM, 512X8, Serial, CMOS, PDSO3")
      (fields
        (field (name "MANUFACTURER") "Microchip")
        (field (name "MANUFACTURER PART NUMBER") "11LC040T-E/TT")
      )
      (libsource (lib "thesis") (part "11LC040T-E/TTTR-ND"))
    )
    (comp (ref "U4")
      (value "Mitochondrik_LV")
      (footprint "Mitochondrik_LV")
      (description "Mitochondrik")
      (libsource (lib "thesis") (part "Mitochondrik_LV"))
    )
    (comp (ref "U5")
      (value "TMP235AEDBZRQ1_1")
      (footprint "TMP235AEDBZRQ1")
      (description "Analog Voltage Output Sensor, 500uA, 2.50Cel, Rectangular, Surface Mount")
      (fields
        (field (name "MANUFACTURER") "Texas Instruments")
        (field (name "MANUFACTURER PART NUMBER") "TMP235AEDBZRQ1")
      )
      (libsource (lib "thesis") (part "TMP235AEDBZRQ1_1"))
    )
  )
  (nets
    (net (code "1") (name "+5") (class "Default")
      (node (ref "C13") (pin "1") (pinfunction "1_1") (pintype "passive"))
      (node (ref "C14") (pin "2") (pinfunction "2_2") (pintype "passive"))
      (node (ref "C18") (pin "2") (pinfunction "2_2") (pintype "passive"))
      (node (ref "C20") (pin "2") (pinfunction "2_2") (pintype "passive"))
      (node (ref "C21") (pin "1") (pinfunction "1_1") (pintype "passive"))
      (node (ref "D13") (pin "2") (pinfunction "cathode(diode_2)_2") (pintype "passive"))
      (node (ref "D13") (pin "5") (pinfunction "cathode(diode_4)_5") (pintype "passive"))
      (node (ref "D14") (pin "A") (pinfunction "A_A") (pintype "passive"))
      (node (ref "D15") (pin "A") (pinfunction "A_A") (pintype "passive"))
      (node (ref "D16") (pin "4") (pinfunction "A_4") (pintype "passive"))
      (node (ref "D18") (pin "1") (pinfunction "K_1") (pintype "passive"))
      (node (ref "F1") (pin "2") (pinfunction "2_2") (pintype "passive"))
      (node (ref "J3") (pin "1") (pinfunction "1_1") (pintype "passive"))
      (node (ref "R24") (pin "1") (pinfunction "1_1") (pintype "passive"))
      (node (ref "R25") (pin "2") (pinfunction "2_2") (pintype "passive"))
      (node (ref "Tele_4") (pin "1") (pinfunction "1_1") (pintype "passive"))
      (node (ref "U1") (pin "3") (pinfunction "Vdd_3") (pintype "passive"))
      (node (ref "U2") (pin "5") (pinfunction "IN_5") (pintype "power_in"))
      (node (ref "U3") (pin "2") (pinfunction "Vcc_2") (pintype "passive"))
      (node (ref "U4") (pin "40") (pinfunction "5V_OUT_40") (pintype "passive"))
      (node (ref "U5") (pin "1") (pinfunction "1_1") (pintype "power_in"))
    )
    (net (code "2") (name "/BEC_ENABLE_OUT") (class "Default")
      (node (ref "U2") (pin "4") (pinfunction "ON_4") (pintype "input"))
      (node (ref "U4") (pin "21") (pinfunction "BEC_ENABLE_OUT_21") (pintype "passive"))
    )
    (net (code "3") (name "/CAN1_LED") (class "Default")
      (node (ref "R25") (pin "1") (pinfunction "1_1") (pintype "passive"))
      (node (ref "R30") (pin "1") (pinfunction "1_1") (pintype "passive"))
      (node (ref "U3") (pin "1") (pinfunction "SCIO_1") (pintype "passive"))
      (node (ref "U4") (pin "33") (pinfunction "CAN1_LED_33") (pintype "passive"))
    )
    (net (code "4") (name "/CAN1_N") (class "Default")
      (node (ref "U1") (pin "4") (pinfunction "RXD_4") (pintype "passive"))
      (node (ref "U4") (pin "38") (pinfunction "CAN1_RX_38") (pintype "passive"))
    )
    (net (code "5") (name "/CAN1_P") (class "Default")
      (node (ref "U1") (pin "1") (pinfunction "TXD_1") (pintype "passive"))
      (node (ref "U4") (pin "39") (pinfunction "CAN1_TX_39") (pintype "passive"))
    )
    (net (code "6") (name "/CAN2_RX") (class "Default")
      (node (ref "U4") (pin "36") (pinfunction "CAN2_RX_36") (pintype "passive"))
    )
    (net (code "7") (name "/CAN2_TX") (class "Default")
      (node (ref "U4") (pin "37") (pinfunction "CAN2_TX_37") (pintype "passive"))
    )
    (net (code "8") (name "/CAN_N") (class "Default")
      (node (ref "Tele_1") (pin "3") (pinfunction "3_3") (pintype "passive"))
      (node (ref "Tele_2") (pin "3") (pinfunction "3_3") (pintype "passive"))
      (node (ref "U1") (pin "6") (pinfunction "CANL_6") (pintype "passive"))
    )
    (net (code "9") (name "/CAN_P") (class "Default")
      (node (ref "Tele_1") (pin "2") (pinfunction "2_2") (pintype "passive"))
      (node (ref "Tele_2") (pin "2") (pinfunction "2_2") (pintype "passive"))
      (node (ref "U1") (pin "7") (pinfunction "CANH_7") (pintype "passive"))
    )
    (net (code "10") (name "/GAIN_OUT") (class "Default")
      (node (ref "D15") (pin "C") (pinfunction "C_C") (pintype "passive"))
      (node (ref "U4") (pin "22") (pinfunction "GAIN_OUT_22") (pintype "passive"))
    )
    (net (code "11") (name "/GATE_ENABLE_OUT") (class "Default")
      (node (ref "D17") (pin "A") (pinfunction "A_A") (pintype "passive"))
      (node (ref "U4") (pin "23") (pinfunction "GATE_ENABLE_OUT_23") (pintype "passive"))
    )
    (net (code "12") (name "/GPIO1") (class "Default")
      (node (ref "J1") (pin "1") (pinfunction "1_1") (pintype "passive"))
      (node (ref "R28") (pin "1") (pinfunction "1_1") (pintype "passive"))
      (node (ref "U4") (pin "25") (pinfunction "GPIO1_25") (pintype "passive"))
    )
    (net (code "13") (name "/GPIO2") (class "Default")
      (node (ref "R29") (pin "1") (pinfunction "1_1") (pintype "passive"))
      (node (ref "U4") (pin "24") (pinfunction "GPIO2_24") (pintype "passive"))
    )
    (net (code "14") (name "/OVERCURRENT") (class "Default")
      (node (ref "R34") (pin "1") (pinfunction "1_1") (pintype "passive"))
      (node (ref "U4") (pin "26") (pinfunction "OVERCURRENT_PROTECT_ADJ_26") (pintype "passive"))
    )
    (net (code "15") (name "/Phase_a") (class "Default")
      (node (ref "A") (pin "1") (pinfunction "1_1") (pintype "passive"))
      (node (ref "D1") (pin "2") (pinfunction "A_2") (pintype "passive"))
      (node (ref "Q1") (pin "1") (pinfunction "S_1") (pintype "passive"))
      (node (ref "Q2") (pin "1") (pinfunction "S_1") (pintype "passive"))
      (node (ref "Q7") (pin "8") (pinfunction "D_8") (pintype "passive"))
      (node (ref "Q8") (pin "8") (pinfunction "D_8") (pintype "passive"))
      (node (ref "R4") (pin "1") (pinfunction "1_1") (pintype "passive"))
      (node (ref "U4") (pin "2") (pinfunction "PHASE_A_2") (pintype "passive"))
    )
    (net (code "16") (name "/RGB_LED_B") (class "Default")
      (node (ref "D16") (pin "3") (pinfunction "BK_3") (pintype "passive"))
      (node (ref "U4") (pin "29") (pinfunction "RGB_LED_B_29") (pintype "passive"))
    )
    (net (code "17") (name "/RGB_LED_G") (class "Default")
      (node (ref "D16") (pin "2") (pinfunction "GK_2") (pintype "passive"))
      (node (ref "U4") (pin "28") (pinfunction "RGB_LED_G_28") (pintype "passive"))
    )
    (net (code "18") (name "/RGB_LED_R") (class "Default")
      (node (ref "D16") (pin "1") (pinfunction "RK_1") (pintype "passive"))
      (node (ref "U4") (pin "27") (pinfunction "RGB_LED_R_27") (pintype "passive"))
    )
    (net (code "19") (name "/UART_N") (class "Default")
      (node (ref "R23") (pin "1") (pinfunction "1_1") (pintype "passive"))
      (node (ref "U4") (pin "19") (pinfunction "UART_TX_19") (pintype "passive"))
    )
    (net (code "20") (name "/UART_P") (class "Default")
      (node (ref "R22") (pin "1") (pinfunction "1_1") (pintype "passive"))
      (node (ref "U4") (pin "20") (pinfunction "UART_RX_20") (pintype "passive"))
    )
    (net (code "21") (name "/USB1_N") (class "Default")
      (node (ref "R32") (pin "1") (pinfunction "1_1") (pintype "passive"))
      (node (ref "U4") (pin "31") (pinfunction "USB-_31") (pintype "passive"))
    )
    (net (code "22") (name "/USB1_P") (class "Default")
      (node (ref "R33") (pin "1") (pinfunction "1_1") (pintype "passive"))
      (node (ref "U4") (pin "32") (pinfunction "USB+_32") (pintype "passive"))
    )
    (net (code "23") (name "/USB_N") (class "Default")
      (node (ref "D19") (pin "3") (pinfunction "3_3") (pintype "passive"))
      (node (ref "J2") (pin "2") (pinfunction "D-_2") (pintype "passive"))
      (node (ref "R32") (pin "2") (pinfunction "2_2") (pintype "passive"))
    )
    (net (code "24") (name "/USB_P") (class "Default")
      (node (ref "D19") (pin "2") (pinfunction "2_2") (pintype "passive"))
      (node (ref "J2") (pin "3") (pinfunction "D+_3") (pintype "passive"))
      (node (ref "R33") (pin "2") (pinfunction "2_2") (pintype "passive"))
    )
    (net (code "25") (name "/USB_VBUS") (class "Default")
      (node (ref "R31") (pin "1") (pinfunction "1_1") (pintype "passive"))
      (node (ref "U4") (pin "30") (pinfunction "USB_VBUS_30") (pintype "passive"))
    )
    (net (code "26") (name "/VBUS") (class "Default")
      (node (ref "D18") (pin "2") (pinfunction "A_2") (pintype "passive"))
      (node (ref "D19") (pin "4") (pinfunction "4_4") (pintype "passive"))
      (node (ref "J2") (pin "1") (pinfunction "VBUS_1") (pintype "passive"))
      (node (ref "R31") (pin "2") (pinfunction "2_2") (pintype "passive"))
    )
    (net (code "27") (name "/phase_a_current_shunt_n") (class "Default")
      (node (ref "R19") (pin "4") (pinfunction "3_4") (pintype "passive"))
      (node (ref "U4") (pin "13") (pinfunction "PHASE_A_CURRENT_SHUNT_N_13") (pintype "passive"))
    )
    (net (code "28") (name "/phase_a_current_shunt_p") (class "Default")
      (node (ref "R19") (pin "3") (pinfunction "3_3") (pintype "passive"))
      (node (ref "U4") (pin "14") (pinfunction "PHASE_A_CURRENT_SHUNT_P_14") (pintype "passive"))
    )
    (net (code "29") (name "/phase_a_gate_high") (class "Default")
      (node (ref "D1") (pin "1") (pinfunction "B_1") (pintype "passive"))
      (node (ref "R1") (pin "1") (pinfunction "1_1") (pintype "passive"))
      (node (ref "R4") (pin "2") (pinfunction "2_2") (pintype "passive"))
      (node (ref "R7") (pin "1") (pinfunction "1_1") (pintype "passive"))
      (node (ref "U4") (pin "1") (pinfunction "PHASE_A_GATE_HIGH_1") (pintype "passive"))
    )
    (net (code "30") (name "/phase_a_gate_low") (class "Default")
      (node (ref "D7") (pin "1") (pinfunction "B_1") (pintype "passive"))
      (node (ref "R10") (pin "1") (pinfunction "1_1") (pintype "passive"))
      (node (ref "R13") (pin "2") (pinfunction "2_2") (pintype "passive"))
      (node (ref "R16") (pin "1") (pinfunction "1_1") (pintype "passive"))
      (node (ref "U4") (pin "3") (pinfunction "PHASE_A_GATE_LOW_3") (pintype "passive"))
    )
    (net (code "31") (name "/phase_a_gnd") (class "Default")
      (node (ref "D7") (pin "2") (pinfunction "A_2") (pintype "passive"))
      (node (ref "Q7") (pin "1") (pinfunction "S_1") (pintype "passive"))
      (node (ref "Q8") (pin "1") (pinfunction "S_1") (pintype "passive"))
      (node (ref "R13") (pin "1") (pinfunction "1_1") (pintype "passive"))
      (node (ref "R19") (pin "2") (pinfunction "2_2") (pintype "passive"))
      (node (ref "U4") (pin "4") (pinfunction "PHASE_A_GND_4") (pintype "passive"))
    )
    (net (code "32") (name "/phase_b") (class "Default")
      (node (ref "B") (pin "1") (pinfunction "1_1") (pintype "passive"))
      (node (ref "D2") (pin "2") (pinfunction "A_2") (pintype "passive"))
      (node (ref "Q10") (pin "8") (pinfunction "D_8") (pintype "passive"))
      (node (ref "Q3") (pin "1") (pinfunction "S_1") (pintype "passive"))
      (node (ref "Q4") (pin "1") (pinfunction "S_1") (pintype "passive"))
      (node (ref "Q9") (pin "8") (pinfunction "D_8") (pintype "passive"))
      (node (ref "R5") (pin "1") (pinfunction "1_1") (pintype "passive"))
      (node (ref "U4") (pin "6") (pinfunction "PHASE_B_6") (pintype "passive"))
    )
    (net (code "33") (name "/phase_b_current_shunt_n") (class "Default")
      (node (ref "R20") (pin "4") (pinfunction "3_4") (pintype "passive"))
      (node (ref "U4") (pin "15") (pinfunction "PHASE_C_CURRENT_SHUNT_N_15") (pintype "passive"))
    )
    (net (code "34") (name "/phase_b_current_shunt_p") (class "Default")
      (node (ref "R20") (pin "3") (pinfunction "3_3") (pintype "passive"))
      (node (ref "U4") (pin "16") (pinfunction "PHASE_C_CURRENT_SHUNT_P_16") (pintype "passive"))
    )
    (net (code "35") (name "/phase_b_gate_high") (class "Default")
      (node (ref "D2") (pin "1") (pinfunction "B_1") (pintype "passive"))
      (node (ref "R2") (pin "1") (pinfunction "1_1") (pintype "passive"))
      (node (ref "R5") (pin "2") (pinfunction "2_2") (pintype "passive"))
      (node (ref "R8") (pin "1") (pinfunction "1_1") (pintype "passive"))
      (node (ref "U4") (pin "5") (pinfunction "PHASE_B_GATE_HIGH_5") (pintype "passive"))
    )
    (net (code "36") (name "/phase_b_gate_low") (class "Default")
      (node (ref "D8") (pin "1") (pinfunction "B_1") (pintype "passive"))
      (node (ref "R11") (pin "1") (pinfunction "1_1") (pintype "passive"))
      (node (ref "R14") (pin "2") (pinfunction "2_2") (pintype "passive"))
      (node (ref "R17") (pin "1") (pinfunction "1_1") (pintype "passive"))
      (node (ref "U4") (pin "7") (pinfunction "PHASE_B_GATE_LOW_7") (pintype "passive"))
    )
    (net (code "37") (name "/phase_b_gnd") (class "Default")
      (node (ref "D8") (pin "2") (pinfunction "A_2") (pintype "passive"))
      (node (ref "Q10") (pin "1") (pinfunction "S_1") (pintype "passive"))
      (node (ref "Q9") (pin "1") (pinfunction "S_1") (pintype "passive"))
      (node (ref "R14") (pin "1") (pinfunction "1_1") (pintype "passive"))
      (node (ref "R20") (pin "2") (pinfunction "2_2") (pintype "passive"))
      (node (ref "U4") (pin "8") (pinfunction "PHASE_B_GND_8") (pintype "passive"))
    )
    (net (code "38") (name "/phase_c") (class "Default")
      (node (ref "C") (pin "1") (pinfunction "1_1") (pintype "passive"))
      (node (ref "D3") (pin "2") (pinfunction "A_2") (pintype "passive"))
      (node (ref "Q11") (pin "8") (pinfunction "D_8") (pintype "passive"))
      (node (ref "Q12") (pin "8") (pinfunction "D_8") (pintype "passive"))
      (node (ref "Q5") (pin "1") (pinfunction "S_1") (pintype "passive"))
      (node (ref "Q6") (pin "1") (pinfunction "S_1") (pintype "passive"))
      (node (ref "R6") (pin "1") (pinfunction "1_1") (pintype "passive"))
      (node (ref "U4") (pin "10") (pinfunction "PHASE_C_10") (pintype "passive"))
    )
    (net (code "39") (name "/phase_c_gate_high") (class "Default")
      (node (ref "D3") (pin "1") (pinfunction "B_1") (pintype "passive"))
      (node (ref "R3") (pin "1") (pinfunction "1_1") (pintype "passive"))
      (node (ref "R6") (pin "2") (pinfunction "2_2") (pintype "passive"))
      (node (ref "R9") (pin "1") (pinfunction "1_1") (pintype "passive"))
      (node (ref "U4") (pin "9") (pinfunction "PHASE_C_GATE_HIGH_9") (pintype "passive"))
    )
    (net (code "40") (name "/phase_c_gate_low") (class "Default")
      (node (ref "D9") (pin "1") (pinfunction "B_1") (pintype "passive"))
      (node (ref "R12") (pin "1") (pinfunction "1_1") (pintype "passive"))
      (node (ref "R15") (pin "2") (pinfunction "2_2") (pintype "passive"))
      (node (ref "R18") (pin "1") (pinfunction "1_1") (pintype "passive"))
      (node (ref "U4") (pin "11") (pinfunction "PHASE_C_GATE_LOW_11") (pintype "passive"))
    )
    (net (code "41") (name "/temperature_sensor") (class "Default")
      (node (ref "C19") (pin "2") (pinfunction "2_2") (pintype "passive"))
      (node (ref "R35") (pin "2") (pinfunction "2_2") (pintype "passive"))
      (node (ref "U4") (pin "17") (pinfunction "TEMPERATURE_SENSOR_17") (pintype "passive"))
    )
    (net (code "42") (name "GND") (class "Default")
      (node (ref "C1") (pin "2") (pinfunction "2_2") (pintype "passive"))
      (node (ref "C10") (pin "2") (pinfunction "2_2") (pintype "passive"))
      (node (ref "C11") (pin "2") (pinfunction "2_2") (pintype "passive"))
      (node (ref "C12") (pin "2") (pinfunction "2_2") (pintype "passive"))
      (node (ref "C13") (pin "2") (pinfunction "2_2") (pintype "passive"))
      (node (ref "C14") (pin "1") (pinfunction "1_1") (pintype "passive"))
      (node (ref "C15") (pin "1") (pinfunction "1_1") (pintype "passive"))
      (node (ref "C16") (pin "1") (pinfunction "1_1") (pintype "passive"))
      (node (ref "C17") (pin "1") (pinfunction "1_1") (pintype "passive"))
      (node (ref "C18") (pin "1") (pinfunction "1_1") (pintype "passive"))
      (node (ref "C19") (pin "1") (pinfunction "1_1") (pintype "passive"))
      (node (ref "C2") (pin "2") (pinfunction "2_2") (pintype "passive"))
      (node (ref "C20") (pin "1") (pinfunction "1_1") (pintype "passive"))
      (node (ref "C21") (pin "2") (pinfunction "2_2") (pintype "passive"))
      (node (ref "C3") (pin "2") (pinfunction "2_2") (pintype "passive"))
      (node (ref "C4") (pin "2") (pinfunction "2_2") (pintype "passive"))
      (node (ref "C5") (pin "2") (pinfunction "2_2") (pintype "passive"))
      (node (ref "C6") (pin "2") (pinfunction "2_2") (pintype "passive"))
      (node (ref "C7") (pin "2") (pinfunction "2_2") (pintype "passive"))
      (node (ref "C8") (pin "2") (pinfunction "2_2") (pintype "passive"))
      (node (ref "C9") (pin "2") (pinfunction "2_2") (pintype "passive"))
      (node (ref "D10") (pin "2") (pinfunction "A_2") (pintype "passive"))
      (node (ref "D11") (pin "2") (pinfunction "A_2") (pintype "passive"))
      (node (ref "D12") (pin "C") (pinfunction "C_C") (pintype "passive"))
      (node (ref "D13") (pin "1") (pinfunction "anode(diode_1)_1") (pintype "passive"))
      (node (ref "D13") (pin "4") (pinfunction "anode(diode_3)_4") (pintype "passive"))
      (node (ref "D17") (pin "C") (pinfunction "C_C") (pintype "passive"))
      (node (ref "D19") (pin "1") (pinfunction "1_1") (pintype "passive"))
      (node (ref "D4") (pin "2") (pinfunction "A_2") (pintype "passive"))
      (node (ref "D5") (pin "2") (pinfunction "A_2") (pintype "passive"))
      (node (ref "D6") (pin "2") (pinfunction "A_2") (pintype "passive"))
      (node (ref "D9") (pin "2") (pinfunction "A_2") (pintype "passive"))
      (node (ref "J1") (pin "2") (pinfunction "2_2") (pintype "passive"))
      (node (ref "J2") (pin "5") (pinfunction "GND_5") (pintype "passive"))
      (node (ref "J3") (pin "2") (pinfunction "2_2") (pintype "passive"))
      (node (ref "J_5") (pin "1") (pinfunction "1_1") (pintype "passive"))
      (node (ref "Q11") (pin "1") (pinfunction "S_1") (pintype "passive"))
      (node (ref "Q12") (pin "1") (pinfunction "S_1") (pintype "passive"))
      (node (ref "Q13") (pin "2") (pinfunction "S_2") (pintype "passive"))
      (node (ref "R15") (pin "1") (pinfunction "1_1") (pintype "passive"))
      (node (ref "R19") (pin "1") (pinfunction "1_1") (pintype "passive"))
      (node (ref "R20") (pin "1") (pinfunction "1_1") (pintype "passive"))
      (node (ref "R27") (pin "1") (pinfunction "1_1") (pintype "passive"))
      (node (ref "R34") (pin "2") (pinfunction "2_2") (pintype "passive"))
      (node (ref "Tele_1") (pin "4") (pinfunction "4_4") (pintype "passive"))
      (node (ref "Tele_2") (pin "4") (pinfunction "4_4") (pintype "passive"))
      (node (ref "Tele_3") (pin "4") (pinfunction "4_4") (pintype "passive"))
      (node (ref "Tele_4") (pin "4") (pinfunction "4_4") (pintype "passive"))
      (node (ref "U1") (pin "2") (pinfunction "Vss_2") (pintype "passive"))
      (node (ref "U1") (pin "8") (pinfunction "STBY_8") (pintype "passive"))
      (node (ref "U2") (pin "2") (pinfunction "GND_2") (pintype "power_in"))
      (node (ref "U3") (pin "3") (pinfunction "Vss_3") (pintype "passive"))
      (node (ref "U4") (pin "12") (pinfunction "PHASE_C_GND_12") (pintype "passive"))
      (node (ref "U4") (pin "41") (pinfunction "GND_41") (pintype "passive"))
      (node (ref "U5") (pin "3") (pinfunction "3_3") (pintype "power_in"))
    )
    (net (code "43") (name "Net-(D10-B)") (class "Default")
      (node (ref "D10") (pin "1") (pinfunction "B_1") (pintype "passive"))
      (node (ref "R23") (pin "2") (pinfunction "2_2") (pintype "passive"))
      (node (ref "Tele_4") (pin "3") (pinfunction "3_3") (pintype "passive"))
    )
    (net (code "44") (name "Net-(D11-B)") (class "Default")
      (node (ref "D11") (pin "1") (pinfunction "B_1") (pintype "passive"))
      (node (ref "R22") (pin "2") (pinfunction "2_2") (pintype "passive"))
      (node (ref "Tele_4") (pin "2") (pinfunction "2_2") (pintype "passive"))
    )
    (net (code "45") (name "Net-(D13-cathode(diode_1){slash}anode(diode_2))") (class "Default")
      (node (ref "D13") (pin "6") (pinfunction "cathode(diode_1)/anode(diode_2)_6") (pintype "passive"))
      (node (ref "R29") (pin "2") (pinfunction "2_2") (pintype "passive"))
      (node (ref "Tele_3") (pin "3") (pinfunction "3_3") (pintype "passive"))
    )
    (net (code "46") (name "Net-(D13-cathode(diode_3){slash}anode(diode_4))") (class "Default")
      (node (ref "D13") (pin "3") (pinfunction "cathode(diode_3)/anode(diode_4)_3") (pintype "passive"))
      (node (ref "R28") (pin "2") (pinfunction "2_2") (pintype "passive"))
      (node (ref "Tele_3") (pin "2") (pinfunction "2_2") (pintype "passive"))
    )
    (net (code "47") (name "Net-(D14-PadC)") (class "Default")
      (node (ref "D14") (pin "C") (pinfunction "C_C") (pintype "passive"))
      (node (ref "R30") (pin "2") (pinfunction "2_2") (pintype "passive"))
    )
    (net (code "48") (name "Net-(F1-Pad1)") (class "Default")
      (node (ref "F1") (pin "1") (pinfunction "1_1") (pintype "passive"))
      (node (ref "Tele_3") (pin "1") (pinfunction "1_1") (pintype "passive"))
    )
    (net (code "49") (name "Net-(Q1-G)") (class "Default")
      (node (ref "Q1") (pin "4") (pinfunction "G_4") (pintype "passive"))
      (node (ref "R7") (pin "2") (pinfunction "2_2") (pintype "passive"))
    )
    (net (code "50") (name "Net-(Q2-G)") (class "Default")
      (node (ref "Q2") (pin "4") (pinfunction "G_4") (pintype "passive"))
      (node (ref "R1") (pin "2") (pinfunction "2_2") (pintype "passive"))
    )
    (net (code "51") (name "Net-(Q3-G)") (class "Default")
      (node (ref "Q3") (pin "4") (pinfunction "G_4") (pintype "passive"))
      (node (ref "R8") (pin "2") (pinfunction "2_2") (pintype "passive"))
    )
    (net (code "52") (name "Net-(Q4-G)") (class "Default")
      (node (ref "Q4") (pin "4") (pinfunction "G_4") (pintype "passive"))
      (node (ref "R2") (pin "2") (pinfunction "2_2") (pintype "passive"))
    )
    (net (code "53") (name "Net-(Q5-G)") (class "Default")
      (node (ref "Q5") (pin "4") (pinfunction "G_4") (pintype "passive"))
      (node (ref "R9") (pin "2") (pinfunction "2_2") (pintype "passive"))
    )
    (net (code "54") (name "Net-(Q6-G)") (class "Default")
      (node (ref "Q6") (pin "4") (pinfunction "G_4") (pintype "passive"))
      (node (ref "R3") (pin "2") (pinfunction "2_2") (pintype "passive"))
    )
    (net (code "55") (name "Net-(Q7-G)") (class "Default")
      (node (ref "Q7") (pin "4") (pinfunction "G_4") (pintype "passive"))
      (node (ref "R16") (pin "2") (pinfunction "2_2") (pintype "passive"))
    )
    (net (code "56") (name "Net-(Q8-G)") (class "Default")
      (node (ref "Q8") (pin "4") (pinfunction "G_4") (pintype "passive"))
      (node (ref "R10") (pin "2") (pinfunction "2_2") (pintype "passive"))
    )
    (net (code "57") (name "Net-(Q9-G)") (class "Default")
      (node (ref "Q9") (pin "4") (pinfunction "G_4") (pintype "passive"))
      (node (ref "R17") (pin "2") (pinfunction "2_2") (pintype "passive"))
    )
    (net (code "58") (name "Net-(Q10-G)") (class "Default")
      (node (ref "Q10") (pin "4") (pinfunction "G_4") (pintype "passive"))
      (node (ref "R11") (pin "2") (pinfunction "2_2") (pintype "passive"))
    )
    (net (code "59") (name "Net-(Q11-G)") (class "Default")
      (node (ref "Q11") (pin "4") (pinfunction "G_4") (pintype "passive"))
      (node (ref "R18") (pin "2") (pinfunction "2_2") (pintype "passive"))
    )
    (net (code "60") (name "Net-(Q12-G)") (class "Default")
      (node (ref "Q12") (pin "4") (pinfunction "G_4") (pintype "passive"))
      (node (ref "R12") (pin "2") (pinfunction "2_2") (pintype "passive"))
    )
    (net (code "61") (name "Net-(Q13-D)") (class "Default")
      (node (ref "D12") (pin "A") (pinfunction "A_A") (pintype "passive"))
      (node (ref "Q13") (pin "3") (pinfunction "D_3") (pintype "passive"))
      (node (ref "R24") (pin "2") (pinfunction "2_2") (pintype "passive"))
    )
    (net (code "62") (name "Net-(Q13-G)") (class "Default")
      (node (ref "Q13") (pin "1") (pinfunction "G_1") (pintype "passive"))
      (node (ref "R26") (pin "2") (pinfunction "2_2") (pintype "passive"))
    )
    (net (code "63") (name "Net-(R35-Pad1)") (class "Default")
      (node (ref "R35") (pin "1") (pinfunction "1_1") (pintype "passive"))
      (node (ref "U5") (pin "2") (pinfunction "2_2") (pintype "output"))
    )
    (net (code "64") (name "Net-(U2-Out)") (class "Default")
      (node (ref "C15") (pin "2") (pinfunction "2_2") (pintype "passive"))
      (node (ref "C16") (pin "2") (pinfunction "2_2") (pintype "passive"))
      (node (ref "C17") (pin "2") (pinfunction "2_2") (pintype "passive"))
      (node (ref "T1") (pin "1") (pinfunction "1_1") (pintype "passive"))
      (node (ref "Tele_1") (pin "1") (pinfunction "1_1") (pintype "passive"))
      (node (ref "Tele_2") (pin "1") (pinfunction "1_1") (pintype "passive"))
      (node (ref "U2") (pin "1") (pinfunction "Out_1") (pintype "power_in"))
    )
    (net (code "65") (name "Net-(U2-SETI)") (class "Default")
      (node (ref "R27") (pin "2") (pinfunction "2_2") (pintype "passive"))
      (node (ref "U2") (pin "3") (pinfunction "SETI_3") (pintype "power_in"))
    )
    (net (code "66") (name "Net-(U2-~{{Flag}})") (class "Default")
      (node (ref "R26") (pin "1") (pinfunction "1_1") (pintype "passive"))
      (node (ref "U2") (pin "6") (pinfunction "~{{Flag}}_6") (pintype "output"))
    )
    (net (code "67") (name "VDC") (class "Default")
      (node (ref "C1") (pin "1") (pinfunction "1_1") (pintype "passive"))
      (node (ref "C10") (pin "1") (pinfunction "1_1") (pintype "passive"))
      (node (ref "C11") (pin "1") (pinfunction "1_1") (pintype "passive"))
      (node (ref "C12") (pin "1") (pinfunction "1_1") (pintype "passive"))
      (node (ref "C2") (pin "1") (pinfunction "1_1") (pintype "passive"))
      (node (ref "C3") (pin "1") (pinfunction "1_1") (pintype "passive"))
      (node (ref "C4") (pin "1") (pinfunction "1_1") (pintype "passive"))
      (node (ref "C5") (pin "1") (pinfunction "1_1") (pintype "passive"))
      (node (ref "C6") (pin "1") (pinfunction "1_1") (pintype "passive"))
      (node (ref "C7") (pin "1") (pinfunction "1_1") (pintype "passive"))
      (node (ref "C8") (pin "1") (pinfunction "1_1") (pintype "passive"))
      (node (ref "C9") (pin "1") (pinfunction "1_1") (pintype "passive"))
      (node (ref "D4") (pin "1") (pinfunction "B_1") (pintype "passive"))
      (node (ref "D5") (pin "1") (pinfunction "B_1") (pintype "passive"))
      (node (ref "D6") (pin "1") (pinfunction "B_1") (pintype "passive"))
      (node (ref "J_1") (pin "1") (pinfunction "1_1") (pintype "passive"))
      (node (ref "Q1") (pin "8") (pinfunction "D_8") (pintype "passive"))
      (node (ref "Q2") (pin "8") (pinfunction "D_8") (pintype "passive"))
      (node (ref "Q3") (pin "8") (pinfunction "D_8") (pintype "passive"))
      (node (ref "Q4") (pin "8") (pinfunction "D_8") (pintype "passive"))
      (node (ref "Q5") (pin "8") (pinfunction "D_8") (pintype "passive"))
      (node (ref "Q6") (pin "8") (pinfunction "D_8") (pintype "passive"))
      (node (ref "U4") (pin "42") (pinfunction "VDC_42") (pintype "passive"))
    )
    (net (code "68") (name "unconnected-(H1-Pad1)") (class "Default")
      (node (ref "H1") (pin "1") (pinfunction "1_1") (pintype "passive"))
    )
    (net (code "69") (name "unconnected-(H2-Pad1)") (class "Default")
      (node (ref "H2") (pin "1") (pinfunction "1_1") (pintype "passive"))
    )
    (net (code "70") (name "unconnected-(J1-MNT_1-Pad3)") (class "Default")
      (node (ref "J1") (pin "3") (pinfunction "MNT_1_3") (pintype "passive+no_connect"))
    )
    (net (code "71") (name "unconnected-(J1-MNT_2-Pad4)") (class "Default")
      (node (ref "J1") (pin "4") (pinfunction "MNT_2_4") (pintype "passive+no_connect"))
    )
    (net (code "72") (name "unconnected-(J2-ID-Pad4)") (class "Default")
      (node (ref "J2") (pin "4") (pinfunction "ID_4") (pintype "passive+no_connect"))
    )
    (net (code "73") (name "unconnected-(J2-SHLD1-Pad6)") (class "Default")
      (node (ref "J2") (pin "6") (pinfunction "SHLD1_6") (pintype "passive+no_connect"))
    )
    (net (code "74") (name "unconnected-(J2-SHLD2-Pad7)") (class "Default")
      (node (ref "J2") (pin "7") (pinfunction "SHLD2_7") (pintype "passive+no_connect"))
    )
    (net (code "75") (name "unconnected-(J2-SHLD3-Pad8)") (class "Default")
      (node (ref "J2") (pin "8") (pinfunction "SHLD3_8") (pintype "passive+no_connect"))
    )
    (net (code "76") (name "unconnected-(J2-SHLD4-Pad9)") (class "Default")
      (node (ref "J2") (pin "9") (pinfunction "SHLD4_9") (pintype "passive+no_connect"))
    )
    (net (code "77") (name "unconnected-(J2-SHLD5-Pad10)") (class "Default")
      (node (ref "J2") (pin "10") (pinfunction "SHLD5_10") (pintype "passive+no_connect"))
    )
    (net (code "78") (name "unconnected-(J2-SHLD6-Pad11)") (class "Default")
      (node (ref "J2") (pin "11") (pinfunction "SHLD6_11") (pintype "passive+no_connect"))
    )
    (net (code "79") (name "unconnected-(J3-MNT_1-Pad3)") (class "Default")
      (node (ref "J3") (pin "3") (pinfunction "MNT_1_3") (pintype "passive+no_connect"))
    )
    (net (code "80") (name "unconnected-(J3-MNT_2-Pad4)") (class "Default")
      (node (ref "J3") (pin "4") (pinfunction "MNT_2_4") (pintype "passive+no_connect"))
    )
    (net (code "81") (name "unconnected-(Tele_1-SHIELD-PadS1)") (class "Default")
      (node (ref "Tele_1") (pin "S1") (pinfunction "SHIELD_S1") (pintype "passive+no_connect"))
    )
    (net (code "82") (name "unconnected-(Tele_1-SHIELD-PadS2)") (class "Default")
      (node (ref "Tele_1") (pin "S2") (pinfunction "SHIELD_S2") (pintype "passive+no_connect"))
    )
    (net (code "83") (name "unconnected-(Tele_2-SHIELD-PadS1)") (class "Default")
      (node (ref "Tele_2") (pin "S1") (pinfunction "SHIELD_S1") (pintype "passive+no_connect"))
    )
    (net (code "84") (name "unconnected-(Tele_2-SHIELD-PadS2)") (class "Default")
      (node (ref "Tele_2") (pin "S2") (pinfunction "SHIELD_S2") (pintype "passive+no_connect"))
    )
    (net (code "85") (name "unconnected-(Tele_3-SHIELD-PadS1)") (class "Default")
      (node (ref "Tele_3") (pin "S1") (pinfunction "SHIELD_S1") (pintype "passive+no_connect"))
    )
    (net (code "86") (name "unconnected-(Tele_3-SHIELD-PadS2)") (class "Default")
      (node (ref "Tele_3") (pin "S2") (pinfunction "SHIELD_S2") (pintype "passive+no_connect"))
    )
    (net (code "87") (name "unconnected-(Tele_4-SHIELD-PadS1)") (class "Default")
      (node (ref "Tele_4") (pin "S1") (pinfunction "SHIELD_S1") (pintype "passive+no_connect"))
    )
    (net (code "88") (name "unconnected-(Tele_4-SHIELD-PadS2)") (class "Default")
      (node (ref "Tele_4") (pin "S2") (pinfunction "SHIELD_S2") (pintype "passive+no_connect"))
    )
    (net (code "89") (name "unconnected-(U1-NC-Pad~)") (class "Default")
      (node (ref "U1") (pin "~") (pinfunction "NC_~") (pintype "passive+no_connect"))
    )
    (net (code "90") (name "unconnected-(U4-CAN2_LED-Pad34)") (class "Default")
      (node (ref "U4") (pin "34") (pinfunction "CAN2_LED_34") (pintype "passive+no_connect"))
    )
    (net (code "91") (name "unconnected-(U4-NC-Pad35)") (class "Default")
      (node (ref "U4") (pin "35") (pinfunction "NC_35") (pintype "passive+no_connect"))
    )
    (net (code "92") (name "unconnected-(U4-POWER_ENABLE_IN-Pad18)") (class "Default")
      (node (ref "U4") (pin "18") (pinfunction "POWER_ENABLE_IN_18") (pintype "passive+no_connect"))
    )
  )
)
